# schematic.net
KiCad netlist of a schematic drawn in EAGLE
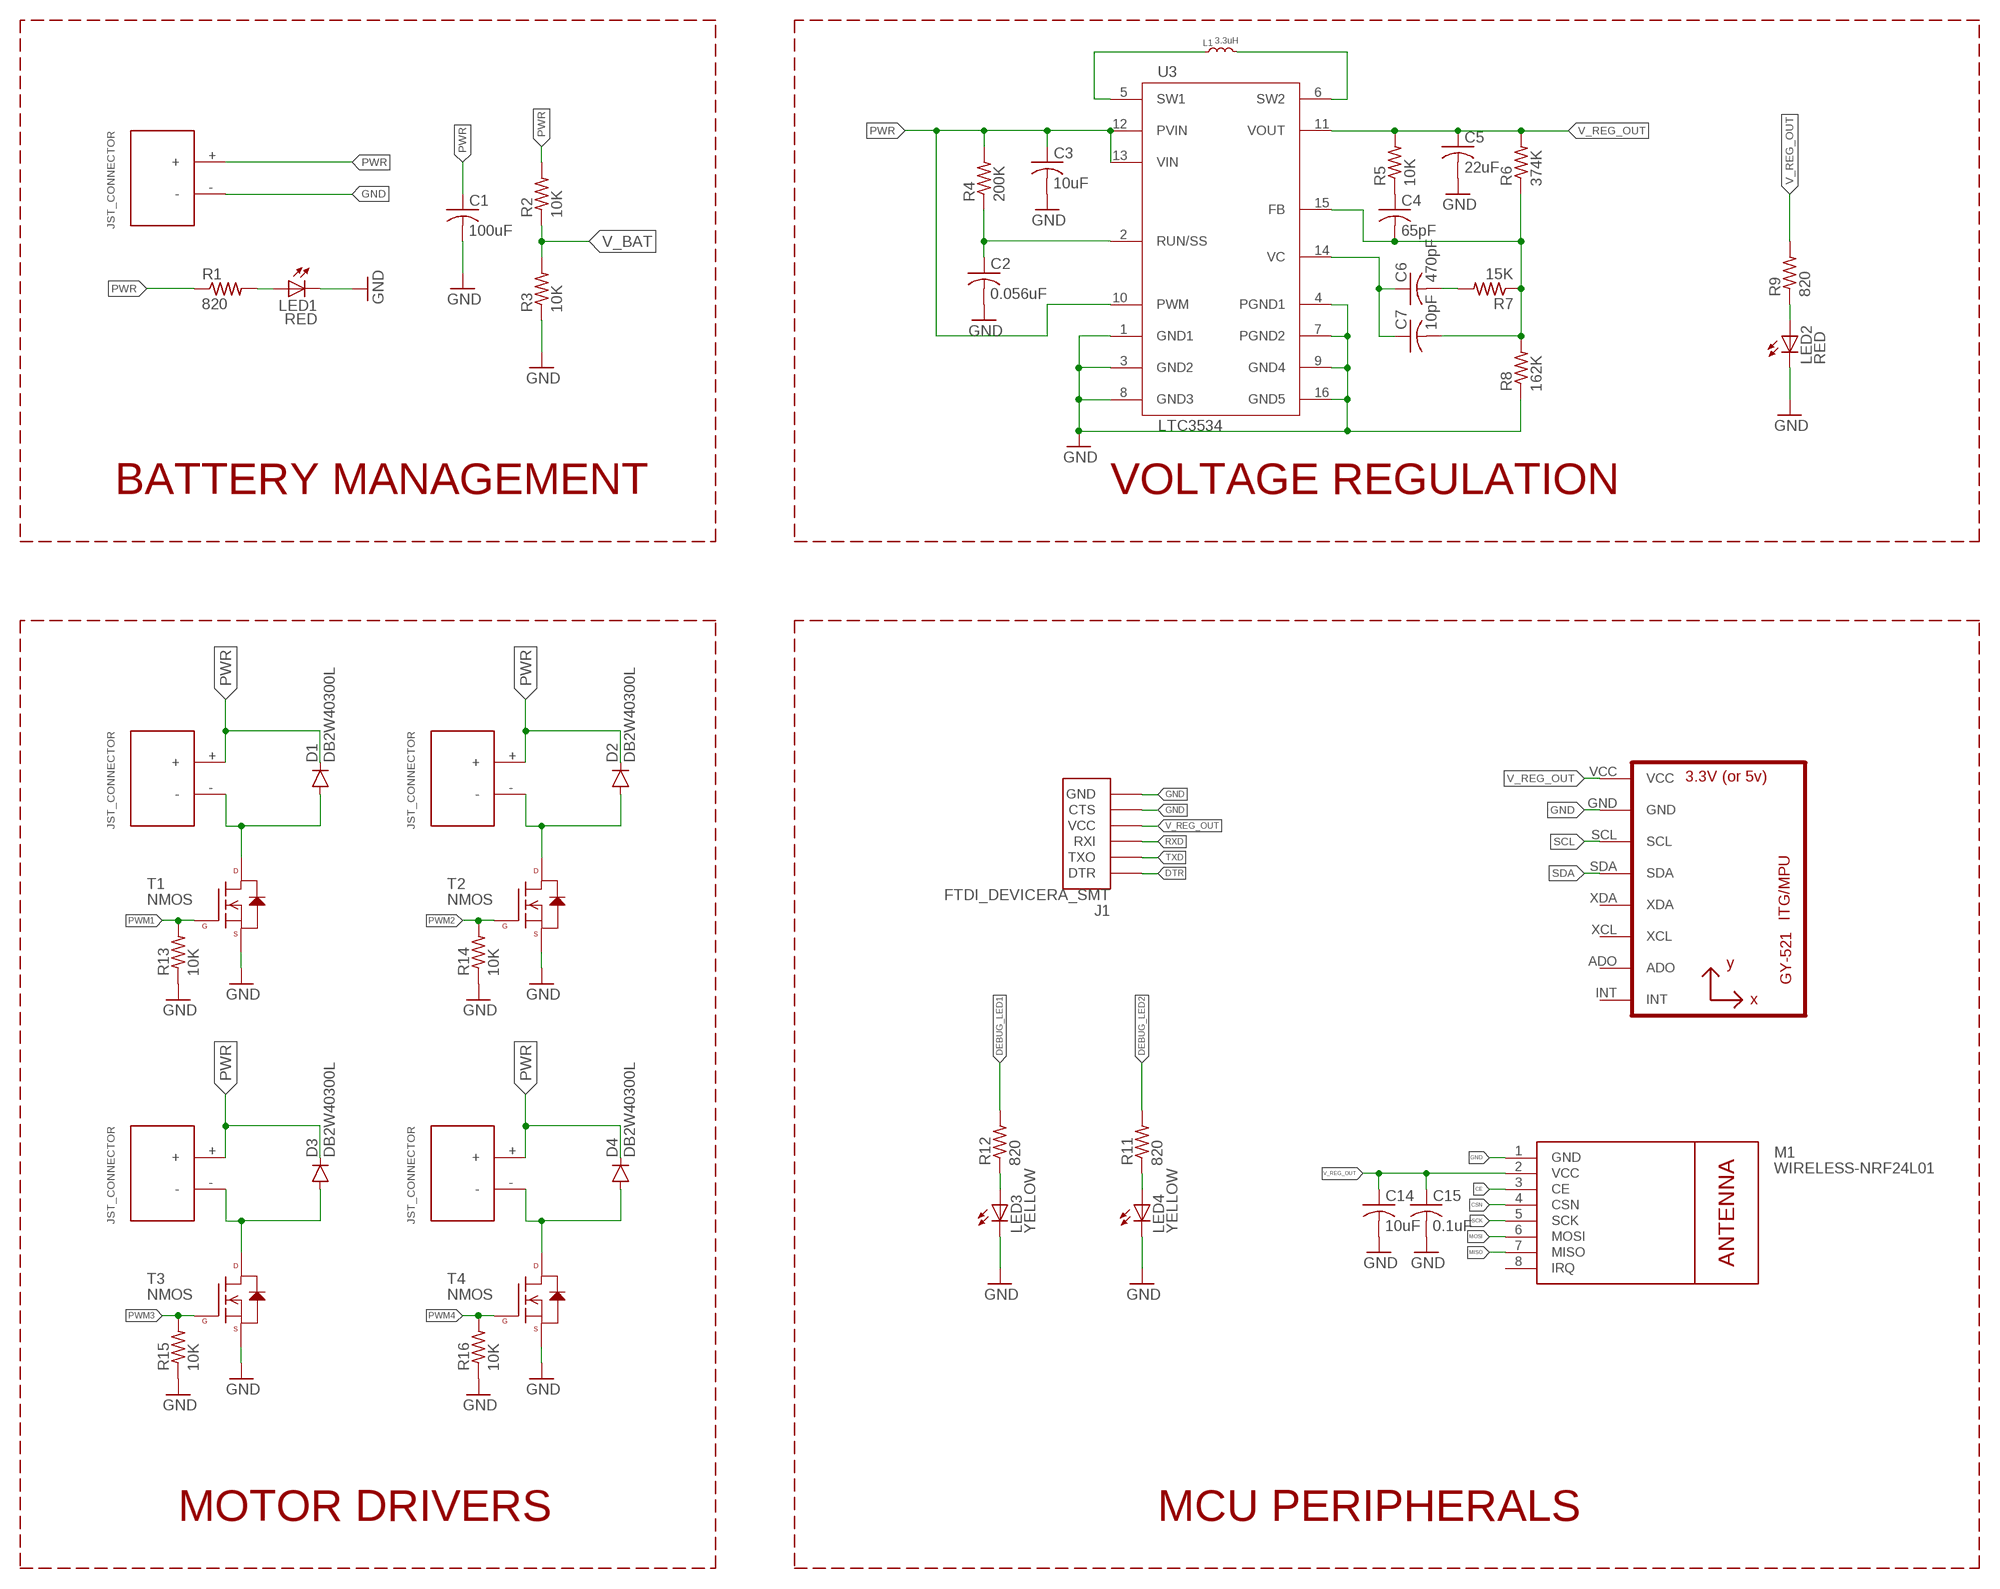
[diagram p0: schematic, sheet 1, part 1 of 2]
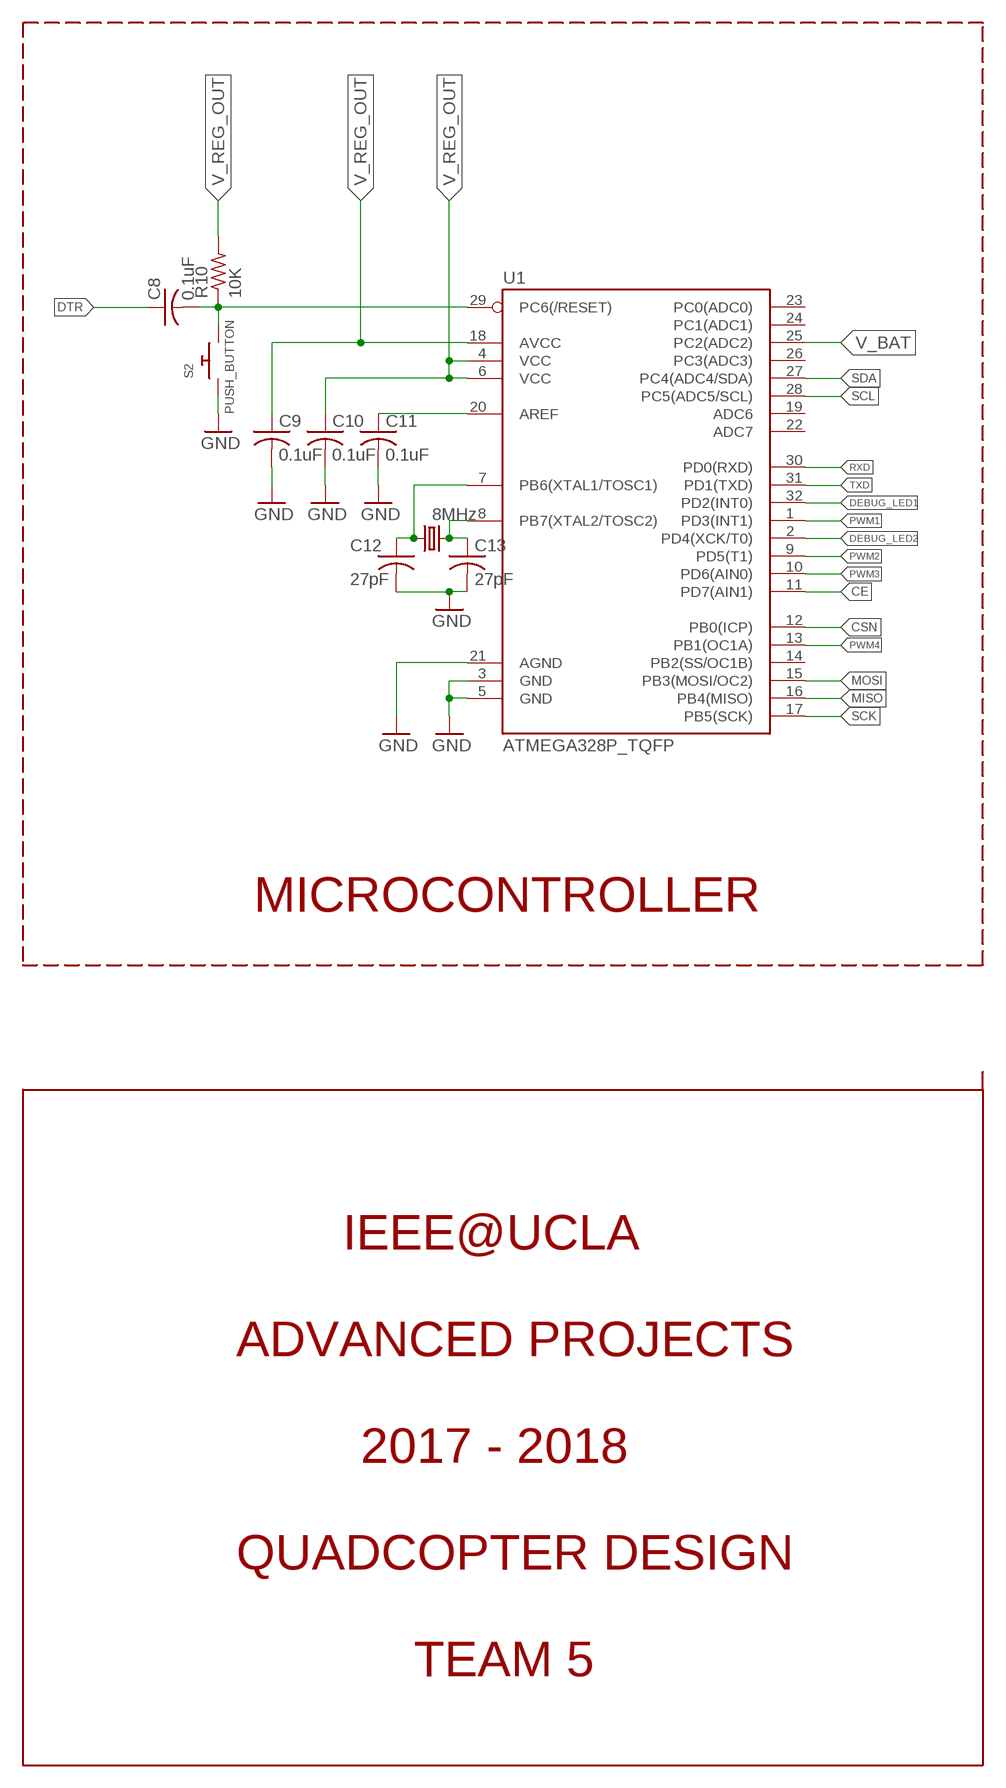
[diagram p1: schematic, sheet 1, part 2 of 2]

(export (version "E")
  (design (tool "Eeschema 10.0.6"))
  (components
    (comp (ref "C1")
      (value "100uF")
      (footprint "eagle-import:C1210")
      (libsource (lib "eagle-import") (part "C-USC1210"))
    )
    (comp (ref "C2")
      (value "0.056uF")
      (footprint "eagle-import:C0603")
      (libsource (lib "eagle-import") (part "resistor_348_C-USC0603"))
    )
    (comp (ref "C3")
      (value "10uF")
      (footprint "eagle-import:C0603")
      (libsource (lib "eagle-import") (part "resistor_348_C-USC0603"))
    )
    (comp (ref "C4")
      (value "65pF")
      (footprint "eagle-import:C1206")
      (libsource (lib "eagle-import") (part "C-USC1206"))
    )
    (comp (ref "C5")
      (value "22uF")
      (footprint "eagle-import:C0603")
      (libsource (lib "eagle-import") (part "resistor_348_C-USC0603"))
    )
    (comp (ref "C6")
      (value "470pF")
      (footprint "eagle-import:C0603")
      (libsource (lib "eagle-import") (part "resistor_348_C-USC0603"))
    )
    (comp (ref "C7")
      (value "10pF")
      (footprint "eagle-import:C0603")
      (libsource (lib "eagle-import") (part "resistor_348_C-USC0603"))
    )
    (comp (ref "C8")
      (value "0.1uF")
      (footprint "eagle-import:C0603")
      (libsource (lib "eagle-import") (part "C-USC0603"))
    )
    (comp (ref "C9")
      (value "0.1uF")
      (footprint "eagle-import:C0603")
      (libsource (lib "eagle-import") (part "C-USC0603"))
    )
    (comp (ref "C10")
      (value "0.1uF")
      (footprint "eagle-import:C0603")
      (libsource (lib "eagle-import") (part "C-USC0603"))
    )
    (comp (ref "C11")
      (value "0.1uF")
      (footprint "eagle-import:C0603")
      (libsource (lib "eagle-import") (part "C-USC0603"))
    )
    (comp (ref "C12")
      (value "27pF")
      (footprint "eagle-import:C0603")
      (libsource (lib "eagle-import") (part "resistor_348_C-USC0603"))
    )
    (comp (ref "C13")
      (value "27pF")
      (footprint "eagle-import:C0603")
      (libsource (lib "eagle-import") (part "resistor_348_C-USC0603"))
    )
    (comp (ref "C14")
      (value "10uF")
      (footprint "eagle-import:C0603")
      (libsource (lib "eagle-import") (part "resistor_348_C-USC0603"))
    )
    (comp (ref "C15")
      (value "0.1uF")
      (footprint "eagle-import:C0603")
      (libsource (lib "eagle-import") (part "resistor_348_C-USC0603"))
    )
    (comp (ref "D1")
      (value "DB2W40300L")
      (footprint "eagle-import:MINI2-F3-B")
      (libsource (lib "eagle-import") (part "DB2W40300L"))
    )
    (comp (ref "D2")
      (value "DB2W40300L")
      (footprint "eagle-import:MINI2-F3-B")
      (libsource (lib "eagle-import") (part "DB2W40300L"))
    )
    (comp (ref "D3")
      (value "DB2W40300L")
      (footprint "eagle-import:MINI2-F3-B")
      (libsource (lib "eagle-import") (part "DB2W40300L"))
    )
    (comp (ref "D4")
      (value "DB2W40300L")
      (footprint "eagle-import:MINI2-F3-B")
      (libsource (lib "eagle-import") (part "DB2W40300L"))
    )
    (comp (ref "J1")
      (value "FTDI_DEVICERA_SMT")
      (footprint "eagle-import:FTDI_DEVICE_RA_SMT")
      (libsource (lib "eagle-import") (part "FTDI_DEVICERA_SMT"))
    )
    (comp (ref "L1")
      (value "3.3uH")
      (footprint "eagle-import:XAL4020")
      (libsource (lib "eagle-import") (part "INDUCTOR.XAL4020"))
    )
    (comp (ref "LED1")
      (value "RED")
      (footprint "eagle-import:SML0603")
      (libsource (lib "eagle-import") (part "LEDSML0603"))
    )
    (comp (ref "LED2")
      (value "RED")
      (footprint "eagle-import:SML0603")
      (libsource (lib "eagle-import") (part "LEDSML0603"))
    )
    (comp (ref "LED3")
      (value "YELLOW")
      (footprint "eagle-import:SML0603")
      (libsource (lib "eagle-import") (part "LEDSML0603"))
    )
    (comp (ref "LED4")
      (value "YELLOW")
      (footprint "eagle-import:SML0603")
      (libsource (lib "eagle-import") (part "LEDSML0603"))
    )
    (comp (ref "M1")
      (value "WIRELESS-NRF24L01")
      (footprint "eagle-import:WIRELESS-NRF24L01")
      (libsource (lib "eagle-import") (part "WIRELESS-NRF24L01"))
    )
    (comp (ref "Q1")
      (value "8MHz")
      (footprint "eagle-import:CSM-7X-DU")
      (libsource (lib "eagle-import") (part "CSM-7X-DU"))
    )
    (comp (ref "R1")
      (value "820")
      (footprint "eagle-import:R0603")
      (libsource (lib "eagle-import") (part "R-US_R0603"))
    )
    (comp (ref "R2")
      (value "10K")
      (footprint "eagle-import:R0603")
      (libsource (lib "eagle-import") (part "resistor_348_R-US_R0603"))
    )
    (comp (ref "R3")
      (value "10K")
      (footprint "eagle-import:R0603")
      (libsource (lib "eagle-import") (part "resistor_348_R-US_R0603"))
    )
    (comp (ref "R4")
      (value "200K")
      (footprint "eagle-import:R0603")
      (libsource (lib "eagle-import") (part "resistor_348_R-US_R0603"))
    )
    (comp (ref "R5")
      (value "10K")
      (footprint "eagle-import:R0603")
      (libsource (lib "eagle-import") (part "resistor_348_R-US_R0603"))
    )
    (comp (ref "R6")
      (value "374K")
      (footprint "eagle-import:R0603")
      (libsource (lib "eagle-import") (part "resistor_348_R-US_R0603"))
    )
    (comp (ref "R7")
      (value "15K")
      (footprint "eagle-import:R0603")
      (libsource (lib "eagle-import") (part "resistor_348_R-US_R0603"))
    )
    (comp (ref "R8")
      (value "162K")
      (footprint "eagle-import:R0603")
      (libsource (lib "eagle-import") (part "resistor_348_R-US_R0603"))
    )
    (comp (ref "R9")
      (value "820")
      (footprint "eagle-import:R0603")
      (libsource (lib "eagle-import") (part "R-US_R0603"))
    )
    (comp (ref "R10")
      (value "10K")
      (footprint "eagle-import:R0603")
      (libsource (lib "eagle-import") (part "resistor_348_R-US_R0603"))
    )
    (comp (ref "R11")
      (value "820")
      (footprint "eagle-import:R0603")
      (libsource (lib "eagle-import") (part "R-US_R0603"))
    )
    (comp (ref "R12")
      (value "820")
      (footprint "eagle-import:R0603")
      (libsource (lib "eagle-import") (part "R-US_R0603"))
    )
    (comp (ref "R13")
      (value "10K")
      (footprint "eagle-import:R0603")
      (libsource (lib "eagle-import") (part "resistor_348_R-US_R0603"))
    )
    (comp (ref "R14")
      (value "10K")
      (footprint "eagle-import:R0603")
      (libsource (lib "eagle-import") (part "resistor_348_R-US_R0603"))
    )
    (comp (ref "R15")
      (value "10K")
      (footprint "eagle-import:R0603")
      (libsource (lib "eagle-import") (part "resistor_348_R-US_R0603"))
    )
    (comp (ref "R16")
      (value "10K")
      (footprint "eagle-import:R0603")
      (libsource (lib "eagle-import") (part "resistor_348_R-US_R0603"))
    )
    (comp (ref "S2")
      (value "PUSH_BUTTON")
      (footprint "eagle-import:PUSHBUTTON_SMD_SJ")
      (libsource (lib "eagle-import") (part "SWITCH_PUSHBUTTONSOFTTOUCHSMD_SJ"))
    )
    (comp (ref "T1")
      (value "NMOS")
      (footprint "eagle-import:SOT23-3")
      (libsource (lib "eagle-import") (part "N-CHANNEL-MOSFET-IRLML6244TRPBF"))
    )
    (comp (ref "T2")
      (value "NMOS")
      (footprint "eagle-import:SOT23-3")
      (libsource (lib "eagle-import") (part "N-CHANNEL-MOSFET-IRLML6244TRPBF"))
    )
    (comp (ref "T3")
      (value "NMOS")
      (footprint "eagle-import:SOT23-3")
      (libsource (lib "eagle-import") (part "N-CHANNEL-MOSFET-IRLML6244TRPBF"))
    )
    (comp (ref "T4")
      (value "NMOS")
      (footprint "eagle-import:SOT23-3")
      (libsource (lib "eagle-import") (part "N-CHANNEL-MOSFET-IRLML6244TRPBF"))
    )
    (comp (ref "U$1")
      (value "JST_CONNECTOR_FEMALE")
      (footprint "eagle-import:JST_CONNECTOR_FEMALE")
      (libsource (lib "eagle-import") (part "JST_CONNECTOR_FEMALE"))
    )
    (comp (ref "U$4")
      (value "JST_CONNECTOR_FEMALE")
      (footprint "eagle-import:JST_CONNECTOR_FEMALE")
      (libsource (lib "eagle-import") (part "JST_CONNECTOR_FEMALE"))
    )
    (comp (ref "U$7")
      (value "JST_CONNECTOR_FEMALE")
      (footprint "eagle-import:JST_CONNECTOR_FEMALE")
      (libsource (lib "eagle-import") (part "JST_CONNECTOR_FEMALE"))
    )
    (comp (ref "U$10")
      (value "JST_CONNECTOR_FEMALE")
      (footprint "eagle-import:JST_CONNECTOR_FEMALE")
      (libsource (lib "eagle-import") (part "JST_CONNECTOR_FEMALE"))
    )
    (comp (ref "U$13")
      (value "JST_CONNECTOR_FEMALE")
      (footprint "eagle-import:JST_CONNECTOR_FEMALE")
      (libsource (lib "eagle-import") (part "JST_CONNECTOR_FEMALE"))
    )
    (comp (ref "U1")
      (value "ATMEGA328P_TQFP")
      (footprint "eagle-import:TQFP32-08")
      (libsource (lib "eagle-import") (part "ATMEGA328P_TQFP"))
    )
    (comp (ref "U2")
      (value "GY-521MPU6050")
      (footprint "eagle-import:GY-521")
      (libsource (lib "eagle-import") (part "GY-521MPU6050"))
    )
    (comp (ref "U3")
      (value "LTC3534")
      (footprint "eagle-import:SSOP-16GN")
      (libsource (lib "eagle-import") (part "LTC3534"))
    )
  )
  (nets
    (net (code "1") (name "CE") (class "Default")
      (node (ref "M1") (pin "3") (pinfunction "CE_3") (pintype "bidirectional"))
      (node (ref "U1") (pin "11") (pinfunction "PD7(AIN1)_11") (pintype "bidirectional"))
    )
    (net (code "2") (name "CSN") (class "Default")
      (node (ref "M1") (pin "4") (pinfunction "CSN_4") (pintype "bidirectional"))
      (node (ref "U1") (pin "12") (pinfunction "PB0(ICP)_12") (pintype "bidirectional"))
    )
    (net (code "3") (name "DEBUG_LED1") (class "Default")
      (node (ref "R12") (pin "2") (pinfunction "2_2") (pintype "passive"))
      (node (ref "U1") (pin "32") (pinfunction "PD2(INT0)_32") (pintype "bidirectional"))
    )
    (net (code "4") (name "DEBUG_LED2") (class "Default")
      (node (ref "R11") (pin "2") (pinfunction "2_2") (pintype "passive"))
      (node (ref "U1") (pin "2") (pinfunction "PD4(XCK/T0)_2") (pintype "bidirectional"))
    )
    (net (code "5") (name "DTR") (class "Default")
      (node (ref "C8") (pin "1") (pinfunction "1_1") (pintype "passive"))
      (node (ref "J1") (pin "1") (pinfunction "DTR_1") (pintype "bidirectional"))
    )
    (net (code "6") (name "GND") (class "Default")
      (node (ref "C1") (pin "2") (pinfunction "2_2") (pintype "passive"))
      (node (ref "C10") (pin "2") (pinfunction "2_2") (pintype "passive"))
      (node (ref "C11") (pin "2") (pinfunction "2_2") (pintype "passive"))
      (node (ref "C12") (pin "2") (pinfunction "2_2") (pintype "passive"))
      (node (ref "C13") (pin "2") (pinfunction "2_2") (pintype "passive"))
      (node (ref "C14") (pin "2") (pinfunction "2_2") (pintype "passive"))
      (node (ref "C15") (pin "2") (pinfunction "2_2") (pintype "passive"))
      (node (ref "C2") (pin "2") (pinfunction "2_2") (pintype "passive"))
      (node (ref "C3") (pin "2") (pinfunction "2_2") (pintype "passive"))
      (node (ref "C5") (pin "2") (pinfunction "2_2") (pintype "passive"))
      (node (ref "C9") (pin "2") (pinfunction "2_2") (pintype "passive"))
      (node (ref "J1") (pin "5") (pinfunction "CTS_5") (pintype "bidirectional"))
      (node (ref "J1") (pin "6") (pinfunction "GND_6") (pintype "bidirectional"))
      (node (ref "LED1") (pin "C") (pinfunction "C_C") (pintype "passive"))
      (node (ref "LED2") (pin "C") (pinfunction "C_C") (pintype "passive"))
      (node (ref "LED3") (pin "C") (pinfunction "C_C") (pintype "passive"))
      (node (ref "LED4") (pin "C") (pinfunction "C_C") (pintype "passive"))
      (node (ref "M1") (pin "1") (pinfunction "GND_1") (pintype "power_in"))
      (node (ref "R13") (pin "1") (pinfunction "1_1") (pintype "passive"))
      (node (ref "R14") (pin "1") (pinfunction "1_1") (pintype "passive"))
      (node (ref "R15") (pin "1") (pinfunction "1_1") (pintype "passive"))
      (node (ref "R16") (pin "1") (pinfunction "1_1") (pintype "passive"))
      (node (ref "R3") (pin "1") (pinfunction "1_1") (pintype "passive"))
      (node (ref "R8") (pin "1") (pinfunction "1_1") (pintype "passive"))
      (node (ref "S2") (pin "P$1") (pinfunction "P$1_P$1") (pintype "passive"))
      (node (ref "T1") (pin "2") (pinfunction "S_2") (pintype "passive"))
      (node (ref "T2") (pin "2") (pinfunction "S_2") (pintype "passive"))
      (node (ref "T3") (pin "2") (pinfunction "S_2") (pintype "passive"))
      (node (ref "T4") (pin "2") (pinfunction "S_2") (pintype "passive"))
      (node (ref "U$1") (pin "-") (pinfunction "-_-") (pintype "bidirectional"))
      (node (ref "U1") (pin "21") (pinfunction "AGND_21") (pintype "bidirectional"))
      (node (ref "U1") (pin "3") (pinfunction "GND_3") (pintype "bidirectional"))
      (node (ref "U1") (pin "5") (pinfunction "GND_5") (pintype "bidirectional"))
      (node (ref "U2") (pin "GND") (pinfunction "GND_GND") (pintype "bidirectional"))
      (node (ref "U3") (pin "1") (pinfunction "GND1_1") (pintype "bidirectional"))
      (node (ref "U3") (pin "16") (pinfunction "GND5_16") (pintype "bidirectional"))
      (node (ref "U3") (pin "3") (pinfunction "GND2_3") (pintype "bidirectional"))
      (node (ref "U3") (pin "4") (pinfunction "PGND1_4") (pintype "bidirectional"))
      (node (ref "U3") (pin "7") (pinfunction "PGND2_7") (pintype "bidirectional"))
      (node (ref "U3") (pin "8") (pinfunction "GND3_8") (pintype "bidirectional"))
      (node (ref "U3") (pin "9") (pinfunction "GND4_9") (pintype "bidirectional"))
    )
    (net (code "7") (name "MISO") (class "Default")
      (node (ref "M1") (pin "7") (pinfunction "MISO_7") (pintype "bidirectional"))
      (node (ref "U1") (pin "16") (pinfunction "PB4(MISO)_16") (pintype "bidirectional"))
    )
    (net (code "8") (name "MOSI") (class "Default")
      (node (ref "M1") (pin "6") (pinfunction "MOSI_6") (pintype "bidirectional"))
      (node (ref "U1") (pin "15") (pinfunction "PB3(MOSI/OC2)_15") (pintype "bidirectional"))
    )
    (net (code "9") (name "Net-(C4-Pad1)") (class "Default")
      (node (ref "C4") (pin "1") (pinfunction "1_1") (pintype "passive"))
      (node (ref "R5") (pin "1") (pinfunction "1_1") (pintype "passive"))
    )
    (net (code "10") (name "Net-(C6-Pad2)") (class "Default")
      (node (ref "C6") (pin "2") (pinfunction "2_2") (pintype "passive"))
      (node (ref "R7") (pin "2") (pinfunction "2_2") (pintype "passive"))
    )
    (net (code "11") (name "Net-(D1-PPIN)") (class "Default")
      (node (ref "D1") (pin "POS") (pinfunction "PPIN_POS") (pintype "passive"))
      (node (ref "T1") (pin "3") (pinfunction "D_3") (pintype "passive"))
      (node (ref "U$4") (pin "-") (pinfunction "-_-") (pintype "bidirectional"))
    )
    (net (code "12") (name "Net-(D2-PPIN)") (class "Default")
      (node (ref "D2") (pin "POS") (pinfunction "PPIN_POS") (pintype "passive"))
      (node (ref "T2") (pin "3") (pinfunction "D_3") (pintype "passive"))
      (node (ref "U$7") (pin "-") (pinfunction "-_-") (pintype "bidirectional"))
    )
    (net (code "13") (name "Net-(D3-PPIN)") (class "Default")
      (node (ref "D3") (pin "POS") (pinfunction "PPIN_POS") (pintype "passive"))
      (node (ref "T3") (pin "3") (pinfunction "D_3") (pintype "passive"))
      (node (ref "U$10") (pin "-") (pinfunction "-_-") (pintype "bidirectional"))
    )
    (net (code "14") (name "Net-(D4-PPIN)") (class "Default")
      (node (ref "D4") (pin "POS") (pinfunction "PPIN_POS") (pintype "passive"))
      (node (ref "T4") (pin "3") (pinfunction "D_3") (pintype "passive"))
      (node (ref "U$13") (pin "-") (pinfunction "-_-") (pintype "bidirectional"))
    )
    (net (code "15") (name "Net-(LED1-PadA)") (class "Default")
      (node (ref "LED1") (pin "A") (pinfunction "A_A") (pintype "passive"))
      (node (ref "R1") (pin "2") (pinfunction "2_2") (pintype "passive"))
    )
    (net (code "16") (name "Net-(LED2-PadA)") (class "Default")
      (node (ref "LED2") (pin "A") (pinfunction "A_A") (pintype "passive"))
      (node (ref "R9") (pin "1") (pinfunction "1_1") (pintype "passive"))
    )
    (net (code "17") (name "Net-(LED3-PadA)") (class "Default")
      (node (ref "LED3") (pin "A") (pinfunction "A_A") (pintype "passive"))
      (node (ref "R12") (pin "1") (pinfunction "1_1") (pintype "passive"))
    )
    (net (code "18") (name "Net-(LED4-PadA)") (class "Default")
      (node (ref "LED4") (pin "A") (pinfunction "A_A") (pintype "passive"))
      (node (ref "R11") (pin "1") (pinfunction "1_1") (pintype "passive"))
    )
    (net (code "19") (name "Net-(U1-AREF)") (class "Default")
      (node (ref "C11") (pin "1") (pinfunction "1_1") (pintype "passive"))
      (node (ref "U1") (pin "20") (pinfunction "AREF_20") (pintype "bidirectional"))
    )
    (net (code "20") (name "Net-(U1-PB6(XTAL1{slash}TOSC1))") (class "Default")
      (node (ref "C12") (pin "1") (pinfunction "1_1") (pintype "passive"))
      (node (ref "Q1") (pin "1") (pinfunction "1_1") (pintype "passive"))
      (node (ref "U1") (pin "7") (pinfunction "PB6(XTAL1/TOSC1)_7") (pintype "bidirectional"))
    )
    (net (code "21") (name "Net-(U1-PB7(XTAL2{slash}TOSC2))") (class "Default")
      (node (ref "C13") (pin "1") (pinfunction "1_1") (pintype "passive"))
      (node (ref "Q1") (pin "2") (pinfunction "2_2") (pintype "passive"))
      (node (ref "U1") (pin "8") (pinfunction "PB7(XTAL2/TOSC2)_8") (pintype "bidirectional"))
    )
    (net (code "22") (name "Net-(U1-PC6({slash}RESET))") (class "Default")
      (node (ref "C8") (pin "2") (pinfunction "2_2") (pintype "passive"))
      (node (ref "R10") (pin "1") (pinfunction "1_1") (pintype "passive"))
      (node (ref "S2") (pin "P$2") (pinfunction "P$2_P$2") (pintype "passive"))
      (node (ref "U1") (pin "29") (pinfunction "PC6(/RESET)_29") (pintype "bidirectional"))
    )
    (net (code "23") (name "Net-(U3-FB)") (class "Default")
      (node (ref "C4") (pin "2") (pinfunction "2_2") (pintype "passive"))
      (node (ref "C7") (pin "2") (pinfunction "2_2") (pintype "passive"))
      (node (ref "R6") (pin "1") (pinfunction "1_1") (pintype "passive"))
      (node (ref "R7") (pin "1") (pinfunction "1_1") (pintype "passive"))
      (node (ref "R8") (pin "2") (pinfunction "2_2") (pintype "passive"))
      (node (ref "U3") (pin "15") (pinfunction "FB_15") (pintype "bidirectional"))
    )
    (net (code "24") (name "Net-(U3-RUN{slash}SS)") (class "Default")
      (node (ref "C2") (pin "1") (pinfunction "1_1") (pintype "passive"))
      (node (ref "R4") (pin "1") (pinfunction "1_1") (pintype "passive"))
      (node (ref "U3") (pin "2") (pinfunction "RUN/SS_2") (pintype "bidirectional"))
    )
    (net (code "25") (name "Net-(U3-SW1)") (class "Default")
      (node (ref "L1") (pin "1") (pinfunction "1_1") (pintype "passive"))
      (node (ref "U3") (pin "5") (pinfunction "SW1_5") (pintype "bidirectional"))
    )
    (net (code "26") (name "Net-(U3-SW2)") (class "Default")
      (node (ref "L1") (pin "2") (pinfunction "2_2") (pintype "passive"))
      (node (ref "U3") (pin "6") (pinfunction "SW2_6") (pintype "bidirectional"))
    )
    (net (code "27") (name "Net-(U3-VC)") (class "Default")
      (node (ref "C6") (pin "1") (pinfunction "1_1") (pintype "passive"))
      (node (ref "C7") (pin "1") (pinfunction "1_1") (pintype "passive"))
      (node (ref "U3") (pin "14") (pinfunction "VC_14") (pintype "bidirectional"))
    )
    (net (code "28") (name "PWM1") (class "Default")
      (node (ref "R13") (pin "2") (pinfunction "2_2") (pintype "passive"))
      (node (ref "T1") (pin "1") (pinfunction "G_1") (pintype "passive"))
      (node (ref "U1") (pin "1") (pinfunction "PD3(INT1)_1") (pintype "bidirectional"))
    )
    (net (code "29") (name "PWM2") (class "Default")
      (node (ref "R14") (pin "2") (pinfunction "2_2") (pintype "passive"))
      (node (ref "T2") (pin "1") (pinfunction "G_1") (pintype "passive"))
      (node (ref "U1") (pin "9") (pinfunction "PD5(T1)_9") (pintype "bidirectional"))
    )
    (net (code "30") (name "PWM3") (class "Default")
      (node (ref "R15") (pin "2") (pinfunction "2_2") (pintype "passive"))
      (node (ref "T3") (pin "1") (pinfunction "G_1") (pintype "passive"))
      (node (ref "U1") (pin "10") (pinfunction "PD6(AIN0)_10") (pintype "bidirectional"))
    )
    (net (code "31") (name "PWM4") (class "Default")
      (node (ref "R16") (pin "2") (pinfunction "2_2") (pintype "passive"))
      (node (ref "T4") (pin "1") (pinfunction "G_1") (pintype "passive"))
      (node (ref "U1") (pin "13") (pinfunction "PB1(OC1A)_13") (pintype "bidirectional"))
    )
    (net (code "32") (name "PWR") (class "Default")
      (node (ref "C1") (pin "1") (pinfunction "1_1") (pintype "passive"))
      (node (ref "C3") (pin "1") (pinfunction "1_1") (pintype "passive"))
      (node (ref "D1") (pin "NEG") (pinfunction "GPIN_NEG") (pintype "passive"))
      (node (ref "D2") (pin "NEG") (pinfunction "GPIN_NEG") (pintype "passive"))
      (node (ref "D3") (pin "NEG") (pinfunction "GPIN_NEG") (pintype "passive"))
      (node (ref "D4") (pin "NEG") (pinfunction "GPIN_NEG") (pintype "passive"))
      (node (ref "R1") (pin "1") (pinfunction "1_1") (pintype "passive"))
      (node (ref "R2") (pin "2") (pinfunction "2_2") (pintype "passive"))
      (node (ref "R4") (pin "2") (pinfunction "2_2") (pintype "passive"))
      (node (ref "U$1") (pin "+") (pinfunction "+_+") (pintype "bidirectional"))
      (node (ref "U$10") (pin "+") (pinfunction "+_+") (pintype "bidirectional"))
      (node (ref "U$13") (pin "+") (pinfunction "+_+") (pintype "bidirectional"))
      (node (ref "U$4") (pin "+") (pinfunction "+_+") (pintype "bidirectional"))
      (node (ref "U$7") (pin "+") (pinfunction "+_+") (pintype "bidirectional"))
      (node (ref "U3") (pin "10") (pinfunction "PWM_10") (pintype "bidirectional"))
      (node (ref "U3") (pin "12") (pinfunction "PVIN_12") (pintype "bidirectional"))
      (node (ref "U3") (pin "13") (pinfunction "VIN_13") (pintype "bidirectional"))
    )
    (net (code "33") (name "RXD") (class "Default")
      (node (ref "J1") (pin "3") (pinfunction "RXI_3") (pintype "bidirectional"))
      (node (ref "U1") (pin "30") (pinfunction "PD0(RXD)_30") (pintype "bidirectional"))
    )
    (net (code "34") (name "SCK") (class "Default")
      (node (ref "M1") (pin "5") (pinfunction "SCK_5") (pintype "bidirectional"))
      (node (ref "U1") (pin "17") (pinfunction "PB5(SCK)_17") (pintype "bidirectional"))
    )
    (net (code "35") (name "SCL") (class "Default")
      (node (ref "U1") (pin "28") (pinfunction "PC5(ADC5/SCL)_28") (pintype "bidirectional"))
      (node (ref "U2") (pin "SCL") (pinfunction "SCL_SCL") (pintype "bidirectional"))
    )
    (net (code "36") (name "SDA") (class "Default")
      (node (ref "U1") (pin "27") (pinfunction "PC4(ADC4/SDA)_27") (pintype "bidirectional"))
      (node (ref "U2") (pin "SDA") (pinfunction "SDA_SDA") (pintype "bidirectional"))
    )
    (net (code "37") (name "TXD") (class "Default")
      (node (ref "J1") (pin "2") (pinfunction "TXO_2") (pintype "bidirectional"))
      (node (ref "U1") (pin "31") (pinfunction "PD1(TXD)_31") (pintype "bidirectional"))
    )
    (net (code "38") (name "V_BAT") (class "Default")
      (node (ref "R2") (pin "1") (pinfunction "1_1") (pintype "passive"))
      (node (ref "R3") (pin "2") (pinfunction "2_2") (pintype "passive"))
      (node (ref "U1") (pin "25") (pinfunction "PC2(ADC2)_25") (pintype "bidirectional"))
    )
    (net (code "39") (name "V_REG_OUT") (class "Default")
      (node (ref "C10") (pin "1") (pinfunction "1_1") (pintype "passive"))
      (node (ref "C14") (pin "1") (pinfunction "1_1") (pintype "passive"))
      (node (ref "C15") (pin "1") (pinfunction "1_1") (pintype "passive"))
      (node (ref "C5") (pin "1") (pinfunction "1_1") (pintype "passive"))
      (node (ref "C9") (pin "1") (pinfunction "1_1") (pintype "passive"))
      (node (ref "J1") (pin "4") (pinfunction "VCC_4") (pintype "bidirectional"))
      (node (ref "M1") (pin "2") (pinfunction "VCC_2") (pintype "power_in"))
      (node (ref "R10") (pin "2") (pinfunction "2_2") (pintype "passive"))
      (node (ref "R5") (pin "2") (pinfunction "2_2") (pintype "passive"))
      (node (ref "R6") (pin "2") (pinfunction "2_2") (pintype "passive"))
      (node (ref "R9") (pin "2") (pinfunction "2_2") (pintype "passive"))
      (node (ref "U1") (pin "18") (pinfunction "AVCC_18") (pintype "bidirectional"))
      (node (ref "U1") (pin "4") (pinfunction "VCC_4") (pintype "bidirectional"))
      (node (ref "U1") (pin "6") (pinfunction "VCC_6") (pintype "bidirectional"))
      (node (ref "U2") (pin "VCC") (pinfunction "VCC_VCC") (pintype "bidirectional"))
      (node (ref "U3") (pin "11") (pinfunction "VOUT_11") (pintype "bidirectional"))
    )
    (net (code "40") (name "unconnected-(M1-IRQ-Pad8)") (class "Default")
      (node (ref "M1") (pin "8") (pinfunction "IRQ_8") (pintype "bidirectional"))
    )
    (net (code "41") (name "unconnected-(U1-ADC6-Pad19)") (class "Default")
      (node (ref "U1") (pin "19") (pinfunction "ADC6_19") (pintype "bidirectional"))
    )
    (net (code "42") (name "unconnected-(U1-ADC7-Pad22)") (class "Default")
      (node (ref "U1") (pin "22") (pinfunction "ADC7_22") (pintype "bidirectional"))
    )
    (net (code "43") (name "unconnected-(U1-PB2(SS{slash}OC1B)-Pad14)") (class "Default")
      (node (ref "U1") (pin "14") (pinfunction "PB2(SS/OC1B)_14") (pintype "bidirectional"))
    )
    (net (code "44") (name "unconnected-(U1-PC0(ADC0)-Pad23)") (class "Default")
      (node (ref "U1") (pin "23") (pinfunction "PC0(ADC0)_23") (pintype "bidirectional"))
    )
    (net (code "45") (name "unconnected-(U1-PC1(ADC1)-Pad24)") (class "Default")
      (node (ref "U1") (pin "24") (pinfunction "PC1(ADC1)_24") (pintype "bidirectional"))
    )
    (net (code "46") (name "unconnected-(U1-PC3(ADC3)-Pad26)") (class "Default")
      (node (ref "U1") (pin "26") (pinfunction "PC3(ADC3)_26") (pintype "bidirectional"))
    )
    (net (code "47") (name "unconnected-(U2-PadADO)") (class "Default")
      (node (ref "U2") (pin "ADO") (pinfunction "ADO_ADO") (pintype "bidirectional"))
    )
    (net (code "48") (name "unconnected-(U2-PadINT)") (class "Default")
      (node (ref "U2") (pin "INT") (pinfunction "INT_INT") (pintype "bidirectional"))
    )
    (net (code "49") (name "unconnected-(U2-PadXCL)") (class "Default")
      (node (ref "U2") (pin "XCL") (pinfunction "XCL_XCL") (pintype "bidirectional"))
    )
    (net (code "50") (name "unconnected-(U2-PadXDA)") (class "Default")
      (node (ref "U2") (pin "XDA") (pinfunction "XDA_XDA") (pintype "bidirectional"))
    )
  )
)
